# Main_board_rev21_bottom_image.net
KiCad netlist of a schematic drawn in EAGLE
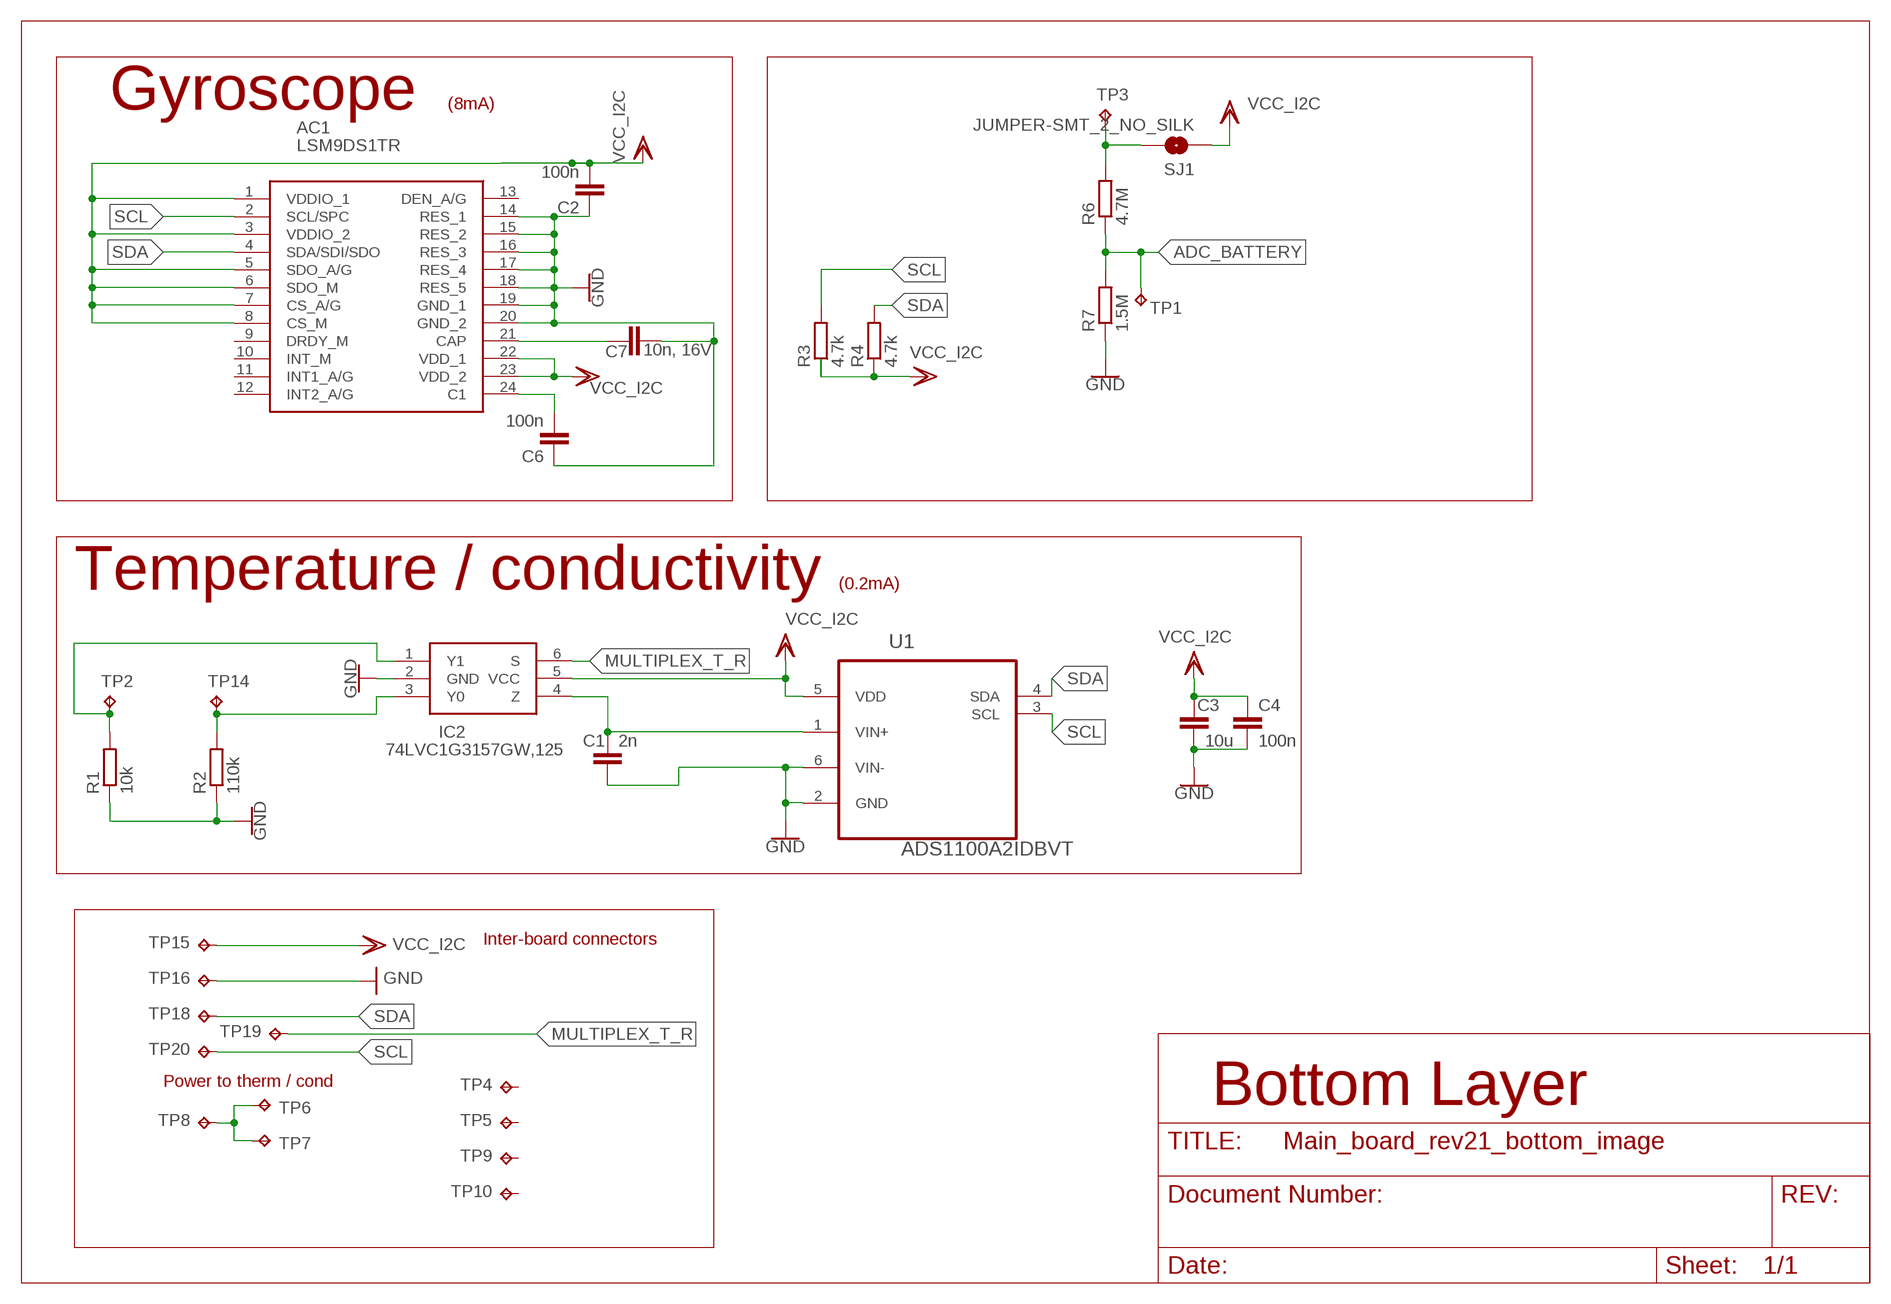
[diagram p0: schematic, sheet 1]

(export (version "E")
  (design (tool "Eeschema 10.0.6"))
  (components
    (comp (ref "AC1")
      (value "LSM9DS1TR")
      (footprint "eagle-import:LGA-24L(3X3.5X1MM)")
      (fields (field (name "MOUSER_PART_NUMBER") "511-LSM9DS1TR"))
      (libsource (lib "eagle-import") (part "LSM9DS1TR"))
    )
    (comp (ref "C1")
      (value "2n")
      (footprint "eagle-import:C0603K")
      (libsource (lib "eagle-import") (part "C-EUC0603K"))
    )
    (comp (ref "C2")
      (value "100n")
      (footprint "eagle-import:C0603K")
      (libsource (lib "eagle-import") (part "C-EUC0603K"))
    )
    (comp (ref "C3")
      (value "10u")
      (footprint "eagle-import:C0603K")
      (libsource (lib "eagle-import") (part "C-EUC0603K"))
    )
    (comp (ref "C4")
      (value "100n")
      (footprint "eagle-import:C0603K")
      (libsource (lib "eagle-import") (part "C-EUC0603K"))
    )
    (comp (ref "C6")
      (value "100n")
      (footprint "eagle-import:C0603K")
      (libsource (lib "eagle-import") (part "C-EUC0603K"))
    )
    (comp (ref "C7")
      (value "10n, 16V")
      (footprint "eagle-import:C0603K")
      (libsource (lib "eagle-import") (part "C-EUC0603K"))
    )
    (comp (ref "IC2")
      (value "74LVC1G3157GW,125")
      (footprint "eagle-import:SOT65P210X110-6N")
      (fields (field (name "MOUSER_PART_NUMBER") "771-LVC1G3157GW125"))
      (libsource (lib "eagle-import") (part "74LVC1G3157GW,125"))
    )
    (comp (ref "R1")
      (value "10k")
      (footprint "eagle-import:R0603")
      (libsource (lib "eagle-import") (part "R-EU_R0603"))
    )
    (comp (ref "R2")
      (value "110k")
      (footprint "eagle-import:R0603")
      (libsource (lib "eagle-import") (part "R-EU_R0603"))
    )
    (comp (ref "R3")
      (value "4.7k")
      (footprint "eagle-import:R0603")
      (libsource (lib "eagle-import") (part "R-EU_R0603"))
    )
    (comp (ref "R4")
      (value "4.7k")
      (footprint "eagle-import:R0603")
      (libsource (lib "eagle-import") (part "R-EU_R0603"))
    )
    (comp (ref "R6")
      (value "4.7M")
      (footprint "eagle-import:R0603")
      (libsource (lib "eagle-import") (part "R-EU_R0603"))
    )
    (comp (ref "R7")
      (value "1.5M")
      (footprint "eagle-import:R0603")
      (libsource (lib "eagle-import") (part "R-EU_R0603"))
    )
    (comp (ref "SJ1")
      (value "JUMPER-SMT_2_NO_SILK")
      (footprint "eagle-import:SMT-JUMPER_2_NO_SILK")
      (libsource (lib "eagle-import") (part "JUMPER-SMT_2_NO_SILK"))
    )
    (comp (ref "TP1")
      (value "TP")
      (footprint "eagle-import:TEST_PAD_1MM")
      (libsource (lib "eagle-import") (part "TP"))
    )
    (comp (ref "TP2")
      (value "TP")
      (footprint "eagle-import:TEST_PAD_1MM")
      (libsource (lib "eagle-import") (part "TP"))
    )
    (comp (ref "TP3")
      (value "TP")
      (footprint "eagle-import:TEST_PAD_1MM")
      (libsource (lib "eagle-import") (part "TP"))
    )
    (comp (ref "TP4")
      (value "TP")
      (footprint "eagle-import:TEST_PAD_1MM")
      (libsource (lib "eagle-import") (part "TP"))
    )
    (comp (ref "TP5")
      (value "TP")
      (footprint "eagle-import:TEST_PAD_1MM")
      (libsource (lib "eagle-import") (part "TP"))
    )
    (comp (ref "TP6")
      (value "TP")
      (footprint "eagle-import:TEST_PAD_1MM")
      (libsource (lib "eagle-import") (part "TP"))
    )
    (comp (ref "TP7")
      (value "TP")
      (footprint "eagle-import:TEST_PAD_1MM")
      (libsource (lib "eagle-import") (part "TP"))
    )
    (comp (ref "TP8")
      (value "TP")
      (footprint "eagle-import:TEST_PAD_1MM")
      (libsource (lib "eagle-import") (part "TP"))
    )
    (comp (ref "TP9")
      (value "TP")
      (footprint "eagle-import:TEST_PAD_1MM")
      (libsource (lib "eagle-import") (part "TP"))
    )
    (comp (ref "TP10")
      (value "TP")
      (footprint "eagle-import:TEST_PAD_1MM")
      (libsource (lib "eagle-import") (part "TP"))
    )
    (comp (ref "TP14")
      (value "TP")
      (footprint "eagle-import:TEST_PAD_1MM")
      (libsource (lib "eagle-import") (part "TP"))
    )
    (comp (ref "TP15")
      (value "TP")
      (footprint "eagle-import:TEST_PAD_1MM")
      (libsource (lib "eagle-import") (part "TP"))
    )
    (comp (ref "TP16")
      (value "TP")
      (footprint "eagle-import:TEST_PAD_1MM")
      (libsource (lib "eagle-import") (part "TP"))
    )
    (comp (ref "TP18")
      (value "TP")
      (footprint "eagle-import:TEST_PAD_1MM")
      (libsource (lib "eagle-import") (part "TP"))
    )
    (comp (ref "TP19")
      (value "TP")
      (footprint "eagle-import:TEST_PAD_1MM")
      (libsource (lib "eagle-import") (part "TP"))
    )
    (comp (ref "TP20")
      (value "TP")
      (footprint "eagle-import:TEST_PAD_1MM")
      (libsource (lib "eagle-import") (part "TP"))
    )
    (comp (ref "U1")
      (value "ADS1100A2IDBVT")
      (footprint "eagle-import:SOT95P280X145-6N")
      (libsource (lib "eagle-import") (part "ADS1100A2IDBVT"))
    )
  )
  (nets
    (net (code "1") (name "ADC_BATTERY") (class "Default")
      (node (ref "R6") (pin "1") (pinfunction "1_1") (pintype "passive"))
      (node (ref "R7") (pin "2") (pinfunction "2_2") (pintype "passive"))
      (node (ref "TP1") (pin "P$1") (pinfunction "TP_P$1") (pintype "input"))
    )
    (net (code "2") (name "GND") (class "Default")
      (node (ref "AC1") (pin "14") (pinfunction "RES_1_14") (pintype "power_in"))
      (node (ref "AC1") (pin "15") (pinfunction "RES_2_15") (pintype "power_in"))
      (node (ref "AC1") (pin "16") (pinfunction "RES_3_16") (pintype "power_in"))
      (node (ref "AC1") (pin "17") (pinfunction "RES_4_17") (pintype "power_in"))
      (node (ref "AC1") (pin "18") (pinfunction "RES_5_18") (pintype "power_in"))
      (node (ref "AC1") (pin "19") (pinfunction "GND_1_19") (pintype "power_in"))
      (node (ref "AC1") (pin "20") (pinfunction "GND_2_20") (pintype "power_in"))
      (node (ref "C1") (pin "2") (pinfunction "2_2") (pintype "passive"))
      (node (ref "C2") (pin "1") (pinfunction "1_1") (pintype "passive"))
      (node (ref "C3") (pin "1") (pinfunction "1_1") (pintype "passive"))
      (node (ref "C4") (pin "2") (pinfunction "2_2") (pintype "passive"))
      (node (ref "C6") (pin "1") (pinfunction "1_1") (pintype "passive"))
      (node (ref "C7") (pin "2") (pinfunction "2_2") (pintype "passive"))
      (node (ref "IC2") (pin "2") (pinfunction "GND_2") (pintype "bidirectional"))
      (node (ref "R1") (pin "1") (pinfunction "1_1") (pintype "passive"))
      (node (ref "R2") (pin "1") (pinfunction "1_1") (pintype "passive"))
      (node (ref "R7") (pin "1") (pinfunction "1_1") (pintype "passive"))
      (node (ref "TP16") (pin "P$1") (pinfunction "TP_P$1") (pintype "input"))
      (node (ref "U1") (pin "2") (pinfunction "GND_2") (pintype "passive"))
      (node (ref "U1") (pin "6") (pinfunction "VIN-_6") (pintype "input"))
    )
    (net (code "3") (name "MULTIPLEX_T_R") (class "Default")
      (node (ref "IC2") (pin "6") (pinfunction "S_6") (pintype "bidirectional"))
      (node (ref "TP19") (pin "P$1") (pinfunction "TP_P$1") (pintype "input"))
    )
    (net (code "4") (name "Net-(AC1-C1)") (class "Default")
      (node (ref "AC1") (pin "24") (pinfunction "C1_24") (pintype "bidirectional"))
      (node (ref "C6") (pin "2") (pinfunction "2_2") (pintype "passive"))
    )
    (net (code "5") (name "Net-(AC1-CAP)") (class "Default")
      (node (ref "AC1") (pin "21") (pinfunction "CAP_21") (pintype "power_in"))
      (node (ref "C7") (pin "1") (pinfunction "1_1") (pintype "passive"))
    )
    (net (code "6") (name "Net-(IC2-Y0)") (class "Default")
      (node (ref "IC2") (pin "3") (pinfunction "Y0_3") (pintype "bidirectional"))
      (node (ref "R2") (pin "2") (pinfunction "2_2") (pintype "passive"))
      (node (ref "TP14") (pin "P$1") (pinfunction "TP_P$1") (pintype "input"))
    )
    (net (code "7") (name "Net-(IC2-Y1)") (class "Default")
      (node (ref "IC2") (pin "1") (pinfunction "Y1_1") (pintype "bidirectional"))
      (node (ref "R1") (pin "2") (pinfunction "2_2") (pintype "passive"))
      (node (ref "TP2") (pin "P$1") (pinfunction "TP_P$1") (pintype "input"))
    )
    (net (code "8") (name "Net-(IC2-Z)") (class "Default")
      (node (ref "C1") (pin "1") (pinfunction "1_1") (pintype "passive"))
      (node (ref "IC2") (pin "4") (pinfunction "Z_4") (pintype "bidirectional"))
      (node (ref "U1") (pin "1") (pinfunction "VIN+_1") (pintype "input"))
    )
    (net (code "9") (name "Net-(TP3-TP)") (class "Default")
      (node (ref "R6") (pin "2") (pinfunction "2_2") (pintype "passive"))
      (node (ref "SJ1") (pin "2") (pinfunction "2_2") (pintype "passive"))
      (node (ref "TP3") (pin "P$1") (pinfunction "TP_P$1") (pintype "input"))
    )
    (net (code "10") (name "Net-(TP6-TP)") (class "Default")
      (node (ref "TP6") (pin "P$1") (pinfunction "TP_P$1") (pintype "input"))
      (node (ref "TP7") (pin "P$1") (pinfunction "TP_P$1") (pintype "input"))
      (node (ref "TP8") (pin "P$1") (pinfunction "TP_P$1") (pintype "input"))
    )
    (net (code "11") (name "SCL") (class "Default")
      (node (ref "AC1") (pin "2") (pinfunction "SCL/SPC_2") (pintype "output"))
      (node (ref "R3") (pin "2") (pinfunction "2_2") (pintype "passive"))
      (node (ref "TP20") (pin "P$1") (pinfunction "TP_P$1") (pintype "input"))
      (node (ref "U1") (pin "3") (pinfunction "SCL_3") (pintype "output"))
    )
    (net (code "12") (name "SDA") (class "Default")
      (node (ref "AC1") (pin "4") (pinfunction "SDA/SDI/SDO_4") (pintype "bidirectional"))
      (node (ref "R4") (pin "2") (pinfunction "2_2") (pintype "passive"))
      (node (ref "TP18") (pin "P$1") (pinfunction "TP_P$1") (pintype "input"))
      (node (ref "U1") (pin "4") (pinfunction "SDA_4") (pintype "output"))
    )
    (net (code "13") (name "VCC_I2C") (class "Default")
      (node (ref "AC1") (pin "1") (pinfunction "VDDIO_1_1") (pintype "power_in"))
      (node (ref "AC1") (pin "22") (pinfunction "VDD_1_22") (pintype "power_in"))
      (node (ref "AC1") (pin "23") (pinfunction "VDD_2_23") (pintype "power_in"))
      (node (ref "AC1") (pin "3") (pinfunction "VDDIO_2_3") (pintype "power_in"))
      (node (ref "AC1") (pin "5") (pinfunction "SDO_A/G_5") (pintype "output"))
      (node (ref "AC1") (pin "6") (pinfunction "SDO_M_6") (pintype "output"))
      (node (ref "AC1") (pin "7") (pinfunction "CS_A/G_7") (pintype "bidirectional"))
      (node (ref "AC1") (pin "8") (pinfunction "CS_M_8") (pintype "bidirectional"))
      (node (ref "C2") (pin "2") (pinfunction "2_2") (pintype "passive"))
      (node (ref "C3") (pin "2") (pinfunction "2_2") (pintype "passive"))
      (node (ref "C4") (pin "1") (pinfunction "1_1") (pintype "passive"))
      (node (ref "IC2") (pin "5") (pinfunction "VCC_5") (pintype "bidirectional"))
      (node (ref "R3") (pin "1") (pinfunction "1_1") (pintype "passive"))
      (node (ref "R4") (pin "1") (pinfunction "1_1") (pintype "passive"))
      (node (ref "SJ1") (pin "1") (pinfunction "1_1") (pintype "passive"))
      (node (ref "TP15") (pin "P$1") (pinfunction "TP_P$1") (pintype "input"))
      (node (ref "U1") (pin "5") (pinfunction "VDD_5") (pintype "power_in"))
    )
    (net (code "14") (name "unconnected-(AC1-DEN_A{slash}G-Pad13)") (class "Default")
      (node (ref "AC1") (pin "13") (pinfunction "DEN_A/G_13") (pintype "bidirectional"))
    )
    (net (code "15") (name "unconnected-(AC1-DRDY_M-Pad9)") (class "Default")
      (node (ref "AC1") (pin "9") (pinfunction "DRDY_M_9") (pintype "bidirectional"))
    )
    (net (code "16") (name "unconnected-(AC1-INT1_A{slash}G-Pad11)") (class "Default")
      (node (ref "AC1") (pin "11") (pinfunction "INT1_A/G_11") (pintype "bidirectional"))
    )
    (net (code "17") (name "unconnected-(AC1-INT2_A{slash}G-Pad12)") (class "Default")
      (node (ref "AC1") (pin "12") (pinfunction "INT2_A/G_12") (pintype "bidirectional"))
    )
    (net (code "18") (name "unconnected-(AC1-INT_M-Pad10)") (class "Default")
      (node (ref "AC1") (pin "10") (pinfunction "INT_M_10") (pintype "bidirectional"))
    )
    (net (code "19") (name "unconnected-(TP4-TP-PadP$1)") (class "Default")
      (node (ref "TP4") (pin "P$1") (pinfunction "TP_P$1") (pintype "input"))
    )
    (net (code "20") (name "unconnected-(TP5-TP-PadP$1)") (class "Default")
      (node (ref "TP5") (pin "P$1") (pinfunction "TP_P$1") (pintype "input"))
    )
    (net (code "21") (name "unconnected-(TP9-TP-PadP$1)") (class "Default")
      (node (ref "TP9") (pin "P$1") (pinfunction "TP_P$1") (pintype "input"))
    )
    (net (code "22") (name "unconnected-(TP10-TP-PadP$1)") (class "Default")
      (node (ref "TP10") (pin "P$1") (pinfunction "TP_P$1") (pintype "input"))
    )
  )
)
